# IntelligentAccessControlSystem.net
KiCad netlist of a schematic drawn in Altium Designer
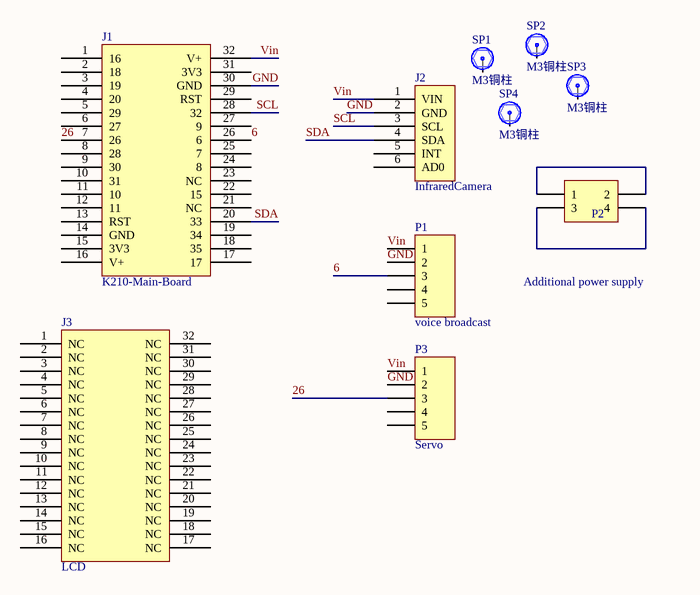
[diagram p0: IntelligentAccessControlSystem.SchDoc]

(export (version "E")
  (design (tool "Eeschema 10.0.6"))
  (components
    (comp (ref "J1")
      (value "K210-Main-Board")
      (footprint "K210-Main-Board")
      (libsource (lib "K210-Main-Board") (part "K210-Main-Board"))
    )
    (comp (ref "J2")
      (value "InfraredCamera")
      (footprint "InfraredCamera")
      (libsource (lib "K210-Main-Board") (part "InfraredCamera"))
    )
    (comp (ref "J3") (value "LCD") (footprint "LCD") (libsource (lib "K210-Main-Board") (part "LCD")))
    (comp (ref "P1")
      (value "voice broadcast")
      (footprint "HDR1X5")
      (description "Header, 5-Pin")
      (fields (field (name "PUBLISHER") "Altium Limited"))
      (libsource (lib "Miscellaneous Connectors") (part "Header 5"))
    )
    (comp (ref "P2")
      (value "Additional power supply")
      (footprint "HDR2X2")
      (description "Header, 2-Pin, Dual row")
      (fields (field (name "PUBLISHER") "Altium Limited"))
      (libsource (lib "Miscellaneous Connectors") (part "Header 2X2"))
    )
    (comp (ref "P3")
      (value "Servo")
      (footprint "HDR1X5")
      (description "Header, 5-Pin")
      (fields (field (name "PUBLISHER") "Altium Limited"))
      (libsource (lib "Miscellaneous Connectors") (part "Header 5"))
    )
    (comp (ref "SP1")
      (value "M3铜柱")
      (footprint "M3x4_L")
      (description "铜柱")
      (libsource (lib "铜柱-测试点-电池座-蜂鸣器") (part "铜柱小焊盘"))
    )
    (comp (ref "SP2")
      (value "M3铜柱")
      (footprint "M3x4_L")
      (description "铜柱")
      (libsource (lib "铜柱-测试点-电池座-蜂鸣器") (part "铜柱小焊盘"))
    )
    (comp (ref "SP3")
      (value "M3铜柱")
      (footprint "M3x4_L")
      (description "铜柱")
      (libsource (lib "铜柱-测试点-电池座-蜂鸣器") (part "铜柱小焊盘"))
    )
    (comp (ref "SP4")
      (value "M3铜柱")
      (footprint "M3x4_L")
      (description "铜柱")
      (libsource (lib "铜柱-测试点-电池座-蜂鸣器") (part "铜柱小焊盘"))
    )
  )
  (nets
    (net (code "1") (name "/6") (class "Default")
      (node (ref "J1") (pin "26") (pinfunction "6_26") (pintype "passive"))
      (node (ref "P1") (pin "3") (pinfunction "3_3") (pintype "passive"))
    )
    (net (code "2") (name "/26") (class "Default")
      (node (ref "J1") (pin "7") (pinfunction "26_7") (pintype "passive"))
      (node (ref "P3") (pin "3") (pinfunction "3_3") (pintype "passive"))
    )
    (net (code "3") (name "/GND") (class "Default")
      (node (ref "J1") (pin "30") (pinfunction "GND_30") (pintype "passive"))
      (node (ref "J2") (pin "2") (pinfunction "GND_2") (pintype "passive"))
      (node (ref "P1") (pin "2") (pinfunction "2_2") (pintype "passive"))
      (node (ref "P3") (pin "2") (pinfunction "2_2") (pintype "passive"))
    )
    (net (code "4") (name "/SCL") (class "Default")
      (node (ref "J1") (pin "28") (pinfunction "32_28") (pintype "passive"))
      (node (ref "J2") (pin "3") (pinfunction "SCL_3") (pintype "passive"))
    )
    (net (code "5") (name "/SDA") (class "Default")
      (node (ref "J1") (pin "20") (pinfunction "33_20") (pintype "passive"))
      (node (ref "J2") (pin "4") (pinfunction "SDA_4") (pintype "passive"))
    )
    (net (code "6") (name "/Vin") (class "Default")
      (node (ref "J1") (pin "32") (pinfunction "V+_32") (pintype "passive"))
      (node (ref "J2") (pin "1") (pinfunction "VIN_1") (pintype "passive"))
      (node (ref "P1") (pin "1") (pinfunction "1_1") (pintype "passive"))
      (node (ref "P3") (pin "1") (pinfunction "1_1") (pintype "passive"))
    )
    (net (code "7") (name "Net-(P2-Pad1)") (class "Default")
      (node (ref "P2") (pin "1") (pinfunction "1_1") (pintype "passive"))
      (node (ref "P2") (pin "2") (pinfunction "2_2") (pintype "passive"))
    )
    (net (code "8") (name "Net-(P2-Pad3)") (class "Default")
      (node (ref "P2") (pin "3") (pinfunction "3_3") (pintype "passive"))
      (node (ref "P2") (pin "4") (pinfunction "4_4") (pintype "passive"))
    )
    (net (code "9") (name "unconnected-(J1-3V3-Pad15)") (class "Default")
      (node (ref "J1") (pin "15") (pinfunction "3V3_15") (pintype "passive"))
    )
    (net (code "10") (name "unconnected-(J1-3V3-Pad31)") (class "Default")
      (node (ref "J1") (pin "31") (pinfunction "3V3_31") (pintype "passive"))
    )
    (net (code "11") (name "unconnected-(J1-7-Pad25)") (class "Default")
      (node (ref "J1") (pin "25") (pinfunction "7_25") (pintype "passive"))
    )
    (net (code "12") (name "unconnected-(J1-8-Pad24)") (class "Default")
      (node (ref "J1") (pin "24") (pinfunction "8_24") (pintype "passive"))
    )
    (net (code "13") (name "unconnected-(J1-9-Pad27)") (class "Default")
      (node (ref "J1") (pin "27") (pinfunction "9_27") (pintype "passive"))
    )
    (net (code "14") (name "unconnected-(J1-10-Pad11)") (class "Default")
      (node (ref "J1") (pin "11") (pinfunction "10_11") (pintype "passive"))
    )
    (net (code "15") (name "unconnected-(J1-11-Pad12)") (class "Default")
      (node (ref "J1") (pin "12") (pinfunction "11_12") (pintype "passive"))
    )
    (net (code "16") (name "unconnected-(J1-15-Pad22)") (class "Default")
      (node (ref "J1") (pin "22") (pinfunction "15_22") (pintype "passive"))
    )
    (net (code "17") (name "unconnected-(J1-16-Pad1)") (class "Default")
      (node (ref "J1") (pin "1") (pinfunction "16_1") (pintype "passive"))
    )
    (net (code "18") (name "unconnected-(J1-18-Pad2)") (class "Default")
      (node (ref "J1") (pin "2") (pinfunction "18_2") (pintype "passive"))
    )
    (net (code "19") (name "unconnected-(J1-19-Pad3)") (class "Default")
      (node (ref "J1") (pin "3") (pinfunction "19_3") (pintype "passive"))
    )
    (net (code "20") (name "unconnected-(J1-20-Pad4)") (class "Default")
      (node (ref "J1") (pin "4") (pinfunction "20_4") (pintype "passive"))
    )
    (net (code "21") (name "unconnected-(J1-27-Pad6)") (class "Default")
      (node (ref "J1") (pin "6") (pinfunction "27_6") (pintype "passive"))
    )
    (net (code "22") (name "unconnected-(J1-28-Pad8)") (class "Default")
      (node (ref "J1") (pin "8") (pinfunction "28_8") (pintype "passive"))
    )
    (net (code "23") (name "unconnected-(J1-29-Pad5)") (class "Default")
      (node (ref "J1") (pin "5") (pinfunction "29_5") (pintype "passive"))
    )
    (net (code "24") (name "unconnected-(J1-30-Pad9)") (class "Default")
      (node (ref "J1") (pin "9") (pinfunction "30_9") (pintype "passive"))
    )
    (net (code "25") (name "unconnected-(J1-31-Pad10)") (class "Default")
      (node (ref "J1") (pin "10") (pinfunction "31_10") (pintype "passive"))
    )
    (net (code "26") (name "unconnected-(J1-34-Pad19)") (class "Default")
      (node (ref "J1") (pin "19") (pinfunction "34_19") (pintype "passive"))
    )
    (net (code "27") (name "unconnected-(J1-35-Pad18)") (class "Default")
      (node (ref "J1") (pin "18") (pinfunction "35_18") (pintype "passive"))
    )
    (net (code "28") (name "unconnected-(J1-GND-Pad14)") (class "Default")
      (node (ref "J1") (pin "14") (pinfunction "GND_14") (pintype "passive"))
    )
    (net (code "29") (name "unconnected-(J1-NC-Pad21)") (class "Default")
      (node (ref "J1") (pin "21") (pinfunction "NC_21") (pintype "passive"))
    )
    (net (code "30") (name "unconnected-(J1-NC-Pad23)") (class "Default")
      (node (ref "J1") (pin "23") (pinfunction "NC_23") (pintype "passive"))
    )
    (net (code "31") (name "unconnected-(J1-Pad17)") (class "Default")
      (node (ref "J1") (pin "17") (pinfunction "17_17") (pintype "passive"))
    )
    (net (code "32") (name "unconnected-(J1-RST-Pad13)") (class "Default")
      (node (ref "J1") (pin "13") (pinfunction "RST_13") (pintype "passive"))
    )
    (net (code "33") (name "unconnected-(J1-RST-Pad29)") (class "Default")
      (node (ref "J1") (pin "29") (pinfunction "RST_29") (pintype "passive"))
    )
    (net (code "34") (name "unconnected-(J1-V+-Pad16)") (class "Default")
      (node (ref "J1") (pin "16") (pinfunction "V+_16") (pintype "passive"))
    )
    (net (code "35") (name "unconnected-(J2-AD0-Pad6)") (class "Default")
      (node (ref "J2") (pin "6") (pinfunction "AD0_6") (pintype "passive"))
    )
    (net (code "36") (name "unconnected-(J2-INT-Pad5)") (class "Default")
      (node (ref "J2") (pin "5") (pinfunction "INT_5") (pintype "passive"))
    )
    (net (code "37") (name "unconnected-(J3-NC-Pad1)") (class "Default")
      (node (ref "J3") (pin "1") (pinfunction "NC_1") (pintype "passive"))
    )
    (net (code "38") (name "unconnected-(J3-NC-Pad2)") (class "Default")
      (node (ref "J3") (pin "2") (pinfunction "NC_2") (pintype "passive"))
    )
    (net (code "39") (name "unconnected-(J3-NC-Pad3)") (class "Default")
      (node (ref "J3") (pin "3") (pinfunction "NC_3") (pintype "passive"))
    )
    (net (code "40") (name "unconnected-(J3-NC-Pad4)") (class "Default")
      (node (ref "J3") (pin "4") (pinfunction "NC_4") (pintype "passive"))
    )
    (net (code "41") (name "unconnected-(J3-NC-Pad5)") (class "Default")
      (node (ref "J3") (pin "5") (pinfunction "NC_5") (pintype "passive"))
    )
    (net (code "42") (name "unconnected-(J3-NC-Pad6)") (class "Default")
      (node (ref "J3") (pin "6") (pinfunction "NC_6") (pintype "passive"))
    )
    (net (code "43") (name "unconnected-(J3-NC-Pad7)") (class "Default")
      (node (ref "J3") (pin "7") (pinfunction "NC_7") (pintype "passive"))
    )
    (net (code "44") (name "unconnected-(J3-NC-Pad8)") (class "Default")
      (node (ref "J3") (pin "8") (pinfunction "NC_8") (pintype "passive"))
    )
    (net (code "45") (name "unconnected-(J3-NC-Pad9)") (class "Default")
      (node (ref "J3") (pin "9") (pinfunction "NC_9") (pintype "passive"))
    )
    (net (code "46") (name "unconnected-(J3-NC-Pad10)") (class "Default")
      (node (ref "J3") (pin "10") (pinfunction "NC_10") (pintype "passive"))
    )
    (net (code "47") (name "unconnected-(J3-NC-Pad11)") (class "Default")
      (node (ref "J3") (pin "11") (pinfunction "NC_11") (pintype "passive"))
    )
    (net (code "48") (name "unconnected-(J3-NC-Pad12)") (class "Default")
      (node (ref "J3") (pin "12") (pinfunction "NC_12") (pintype "passive"))
    )
    (net (code "49") (name "unconnected-(J3-NC-Pad13)") (class "Default")
      (node (ref "J3") (pin "13") (pinfunction "NC_13") (pintype "passive"))
    )
    (net (code "50") (name "unconnected-(J3-NC-Pad14)") (class "Default")
      (node (ref "J3") (pin "14") (pinfunction "NC_14") (pintype "passive"))
    )
    (net (code "51") (name "unconnected-(J3-NC-Pad15)") (class "Default")
      (node (ref "J3") (pin "15") (pinfunction "NC_15") (pintype "passive"))
    )
    (net (code "52") (name "unconnected-(J3-NC-Pad16)") (class "Default")
      (node (ref "J3") (pin "16") (pinfunction "NC_16") (pintype "passive"))
    )
    (net (code "53") (name "unconnected-(J3-NC-Pad17)") (class "Default")
      (node (ref "J3") (pin "17") (pinfunction "NC_17") (pintype "passive"))
    )
    (net (code "54") (name "unconnected-(J3-NC-Pad18)") (class "Default")
      (node (ref "J3") (pin "18") (pinfunction "NC_18") (pintype "passive"))
    )
    (net (code "55") (name "unconnected-(J3-NC-Pad19)") (class "Default")
      (node (ref "J3") (pin "19") (pinfunction "NC_19") (pintype "passive"))
    )
    (net (code "56") (name "unconnected-(J3-NC-Pad20)") (class "Default")
      (node (ref "J3") (pin "20") (pinfunction "NC_20") (pintype "passive"))
    )
    (net (code "57") (name "unconnected-(J3-NC-Pad21)") (class "Default")
      (node (ref "J3") (pin "21") (pinfunction "NC_21") (pintype "passive"))
    )
    (net (code "58") (name "unconnected-(J3-NC-Pad22)") (class "Default")
      (node (ref "J3") (pin "22") (pinfunction "NC_22") (pintype "passive"))
    )
    (net (code "59") (name "unconnected-(J3-NC-Pad23)") (class "Default")
      (node (ref "J3") (pin "23") (pinfunction "NC_23") (pintype "passive"))
    )
    (net (code "60") (name "unconnected-(J3-NC-Pad24)") (class "Default")
      (node (ref "J3") (pin "24") (pinfunction "NC_24") (pintype "passive"))
    )
    (net (code "61") (name "unconnected-(J3-NC-Pad25)") (class "Default")
      (node (ref "J3") (pin "25") (pinfunction "NC_25") (pintype "passive"))
    )
    (net (code "62") (name "unconnected-(J3-NC-Pad26)") (class "Default")
      (node (ref "J3") (pin "26") (pinfunction "NC_26") (pintype "passive"))
    )
    (net (code "63") (name "unconnected-(J3-NC-Pad27)") (class "Default")
      (node (ref "J3") (pin "27") (pinfunction "NC_27") (pintype "passive"))
    )
    (net (code "64") (name "unconnected-(J3-NC-Pad28)") (class "Default")
      (node (ref "J3") (pin "28") (pinfunction "NC_28") (pintype "passive"))
    )
    (net (code "65") (name "unconnected-(J3-NC-Pad29)") (class "Default")
      (node (ref "J3") (pin "29") (pinfunction "NC_29") (pintype "passive"))
    )
    (net (code "66") (name "unconnected-(J3-NC-Pad30)") (class "Default")
      (node (ref "J3") (pin "30") (pinfunction "NC_30") (pintype "passive"))
    )
    (net (code "67") (name "unconnected-(J3-NC-Pad31)") (class "Default")
      (node (ref "J3") (pin "31") (pinfunction "NC_31") (pintype "passive"))
    )
    (net (code "68") (name "unconnected-(J3-NC-Pad32)") (class "Default")
      (node (ref "J3") (pin "32") (pinfunction "NC_32") (pintype "passive"))
    )
    (net (code "69") (name "unconnected-(P1-Pad4)") (class "Default")
      (node (ref "P1") (pin "4") (pinfunction "4_4") (pintype "passive"))
    )
    (net (code "70") (name "unconnected-(P1-Pad5)") (class "Default")
      (node (ref "P1") (pin "5") (pinfunction "5_5") (pintype "passive"))
    )
    (net (code "71") (name "unconnected-(P3-Pad4)") (class "Default")
      (node (ref "P3") (pin "4") (pinfunction "4_4") (pintype "passive"))
    )
    (net (code "72") (name "unconnected-(P3-Pad5)") (class "Default")
      (node (ref "P3") (pin "5") (pinfunction "5_5") (pintype "passive"))
    )
    (net (code "73") (name "unconnected-(SP1-Pad1)") (class "Default")
      (node (ref "SP1") (pin "1") (pinfunction "1_1") (pintype "passive"))
    )
    (net (code "74") (name "unconnected-(SP2-Pad1)") (class "Default")
      (node (ref "SP2") (pin "1") (pinfunction "1_1") (pintype "passive"))
    )
    (net (code "75") (name "unconnected-(SP3-Pad1)") (class "Default")
      (node (ref "SP3") (pin "1") (pinfunction "1_1") (pintype "passive"))
    )
    (net (code "76") (name "unconnected-(SP4-Pad1)") (class "Default")
      (node (ref "SP4") (pin "1") (pinfunction "1_1") (pintype "passive"))
    )
  )
)
